# sim.net
KiCad netlist of a schematic drawn in Altium Designer
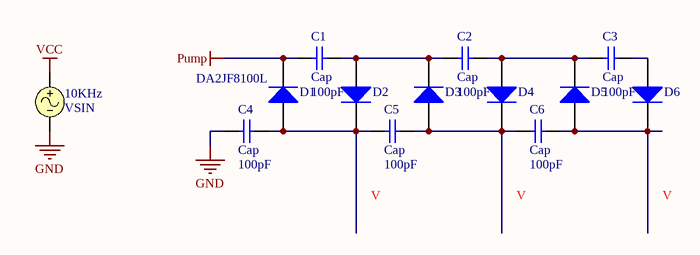
[diagram p0: sim.SchDoc]

(export (version "E")
  (design (tool "Eeschema 10.0.6"))
  (components
    (comp (ref "10KHz")
      (value "VSIN")
      (description "Sinusoidal Voltage Source")
      (fields (field (name "PUBLISHER") "Altium Limited"))
      (libsource (lib "Simulation Sources") (part "VSIN"))
    )
    (comp (ref "C1")
      (value "Cap")
      (footprint "RAD-0.3")
      (description "Capacitor")
      (fields (field (name "ALTIUM_VALUE") "100pF") (field (name "PUBLISHER") "Altium Limited"))
      (libsource (lib "Miscellaneous Devices") (part "Cap"))
    )
    (comp (ref "C2")
      (value "Cap")
      (footprint "RAD-0.3")
      (description "Capacitor")
      (fields (field (name "ALTIUM_VALUE") "100pF") (field (name "PUBLISHER") "Altium Limited"))
      (libsource (lib "Miscellaneous Devices") (part "Cap"))
    )
    (comp (ref "C3")
      (value "Cap")
      (footprint "RAD-0.3")
      (description "Capacitor")
      (fields (field (name "ALTIUM_VALUE") "100pF") (field (name "PUBLISHER") "Altium Limited"))
      (libsource (lib "Miscellaneous Devices") (part "Cap"))
    )
    (comp (ref "C4")
      (value "Cap")
      (footprint "RAD-0.3")
      (description "Capacitor")
      (fields (field (name "ALTIUM_VALUE") "100pF") (field (name "PUBLISHER") "Altium Limited"))
      (libsource (lib "Miscellaneous Devices") (part "Cap"))
    )
    (comp (ref "C5")
      (value "Cap")
      (footprint "RAD-0.3")
      (description "Capacitor")
      (fields (field (name "ALTIUM_VALUE") "100pF") (field (name "PUBLISHER") "Altium Limited"))
      (libsource (lib "Miscellaneous Devices") (part "Cap"))
    )
    (comp (ref "C6")
      (value "Cap")
      (footprint "RAD-0.3")
      (description "Capacitor")
      (fields (field (name "ALTIUM_VALUE") "100pF") (field (name "PUBLISHER") "Altium Limited"))
      (libsource (lib "Miscellaneous Devices") (part "Cap"))
    )
    (comp (ref "D1")
      (value "DA2JF8100L")
      (footprint "DA2JF8100L")
      (description "Default Diode")
      (fields (field (name "PUBLISHER") "Altium Limited"))
      (libsource (lib "Miscellaneous Devices") (part "Diode"))
    )
    (comp (ref "D2")
      (value "~")
      (footprint "DA2JF8100L")
      (description "Default Diode")
      (fields (field (name "PUBLISHER") "Altium Limited"))
      (libsource (lib "Miscellaneous Devices") (part "Diode"))
    )
    (comp (ref "D3")
      (value "~")
      (footprint "DA2JF8100L")
      (description "Default Diode")
      (fields (field (name "PUBLISHER") "Altium Limited"))
      (libsource (lib "Miscellaneous Devices") (part "Diode"))
    )
    (comp (ref "D4")
      (value "~")
      (footprint "DA2JF8100L")
      (description "Default Diode")
      (fields (field (name "PUBLISHER") "Altium Limited"))
      (libsource (lib "Miscellaneous Devices") (part "Diode"))
    )
    (comp (ref "D5")
      (value "~")
      (footprint "DA2JF8100L")
      (description "Default Diode")
      (fields (field (name "PUBLISHER") "Altium Limited"))
      (libsource (lib "Miscellaneous Devices") (part "Diode"))
    )
    (comp (ref "D6")
      (value "~")
      (footprint "DA2JF8100L")
      (description "Default Diode")
      (fields (field (name "PUBLISHER") "Altium Limited"))
      (libsource (lib "Miscellaneous Devices") (part "Diode"))
    )
  )
  (nets
    (net (code "1") (name "GND") (class "Default")
      (node (ref "10KHz") (pin "2") (pinfunction "2_2") (pintype "passive"))
      (node (ref "C4") (pin "1") (pinfunction "1_1") (pintype "passive"))
    )
    (net (code "2") (name "Net-(D1-A)") (class "Default")
      (node (ref "C4") (pin "2") (pinfunction "2_2") (pintype "passive"))
      (node (ref "C5") (pin "1") (pinfunction "1_1") (pintype "passive"))
      (node (ref "D1") (pin "1") (pinfunction "A_1") (pintype "passive"))
      (node (ref "D2") (pin "2") (pinfunction "K_2") (pintype "passive"))
    )
    (net (code "3") (name "Net-(D2-A)") (class "Default")
      (node (ref "C1") (pin "2") (pinfunction "2_2") (pintype "passive"))
      (node (ref "C2") (pin "1") (pinfunction "1_1") (pintype "passive"))
      (node (ref "D2") (pin "1") (pinfunction "A_1") (pintype "passive"))
      (node (ref "D3") (pin "2") (pinfunction "K_2") (pintype "passive"))
    )
    (net (code "4") (name "Net-(D3-A)") (class "Default")
      (node (ref "C5") (pin "2") (pinfunction "2_2") (pintype "passive"))
      (node (ref "C6") (pin "1") (pinfunction "1_1") (pintype "passive"))
      (node (ref "D3") (pin "1") (pinfunction "A_1") (pintype "passive"))
      (node (ref "D4") (pin "2") (pinfunction "K_2") (pintype "passive"))
    )
    (net (code "5") (name "Net-(D4-A)") (class "Default")
      (node (ref "C2") (pin "2") (pinfunction "2_2") (pintype "passive"))
      (node (ref "C3") (pin "1") (pinfunction "1_1") (pintype "passive"))
      (node (ref "D4") (pin "1") (pinfunction "A_1") (pintype "passive"))
      (node (ref "D5") (pin "2") (pinfunction "K_2") (pintype "passive"))
    )
    (net (code "6") (name "Net-(D5-A)") (class "Default")
      (node (ref "C6") (pin "2") (pinfunction "2_2") (pintype "passive"))
      (node (ref "D5") (pin "1") (pinfunction "A_1") (pintype "passive"))
      (node (ref "D6") (pin "2") (pinfunction "K_2") (pintype "passive"))
    )
    (net (code "7") (name "Net-(D6-A)") (class "Default")
      (node (ref "C3") (pin "2") (pinfunction "2_2") (pintype "passive"))
      (node (ref "D6") (pin "1") (pinfunction "A_1") (pintype "passive"))
    )
    (net (code "8") (name "Pump") (class "Default")
      (node (ref "C1") (pin "1") (pinfunction "1_1") (pintype "passive"))
      (node (ref "D1") (pin "2") (pinfunction "K_2") (pintype "passive"))
    )
    (net (code "9") (name "VCC") (class "Default")
      (node (ref "10KHz") (pin "1") (pinfunction "1_1") (pintype "passive"))
    )
  )
)
